# MPBoard_L4_Sens1_ext.net
KiCad netlist of a schematic drawn in Altium Designer
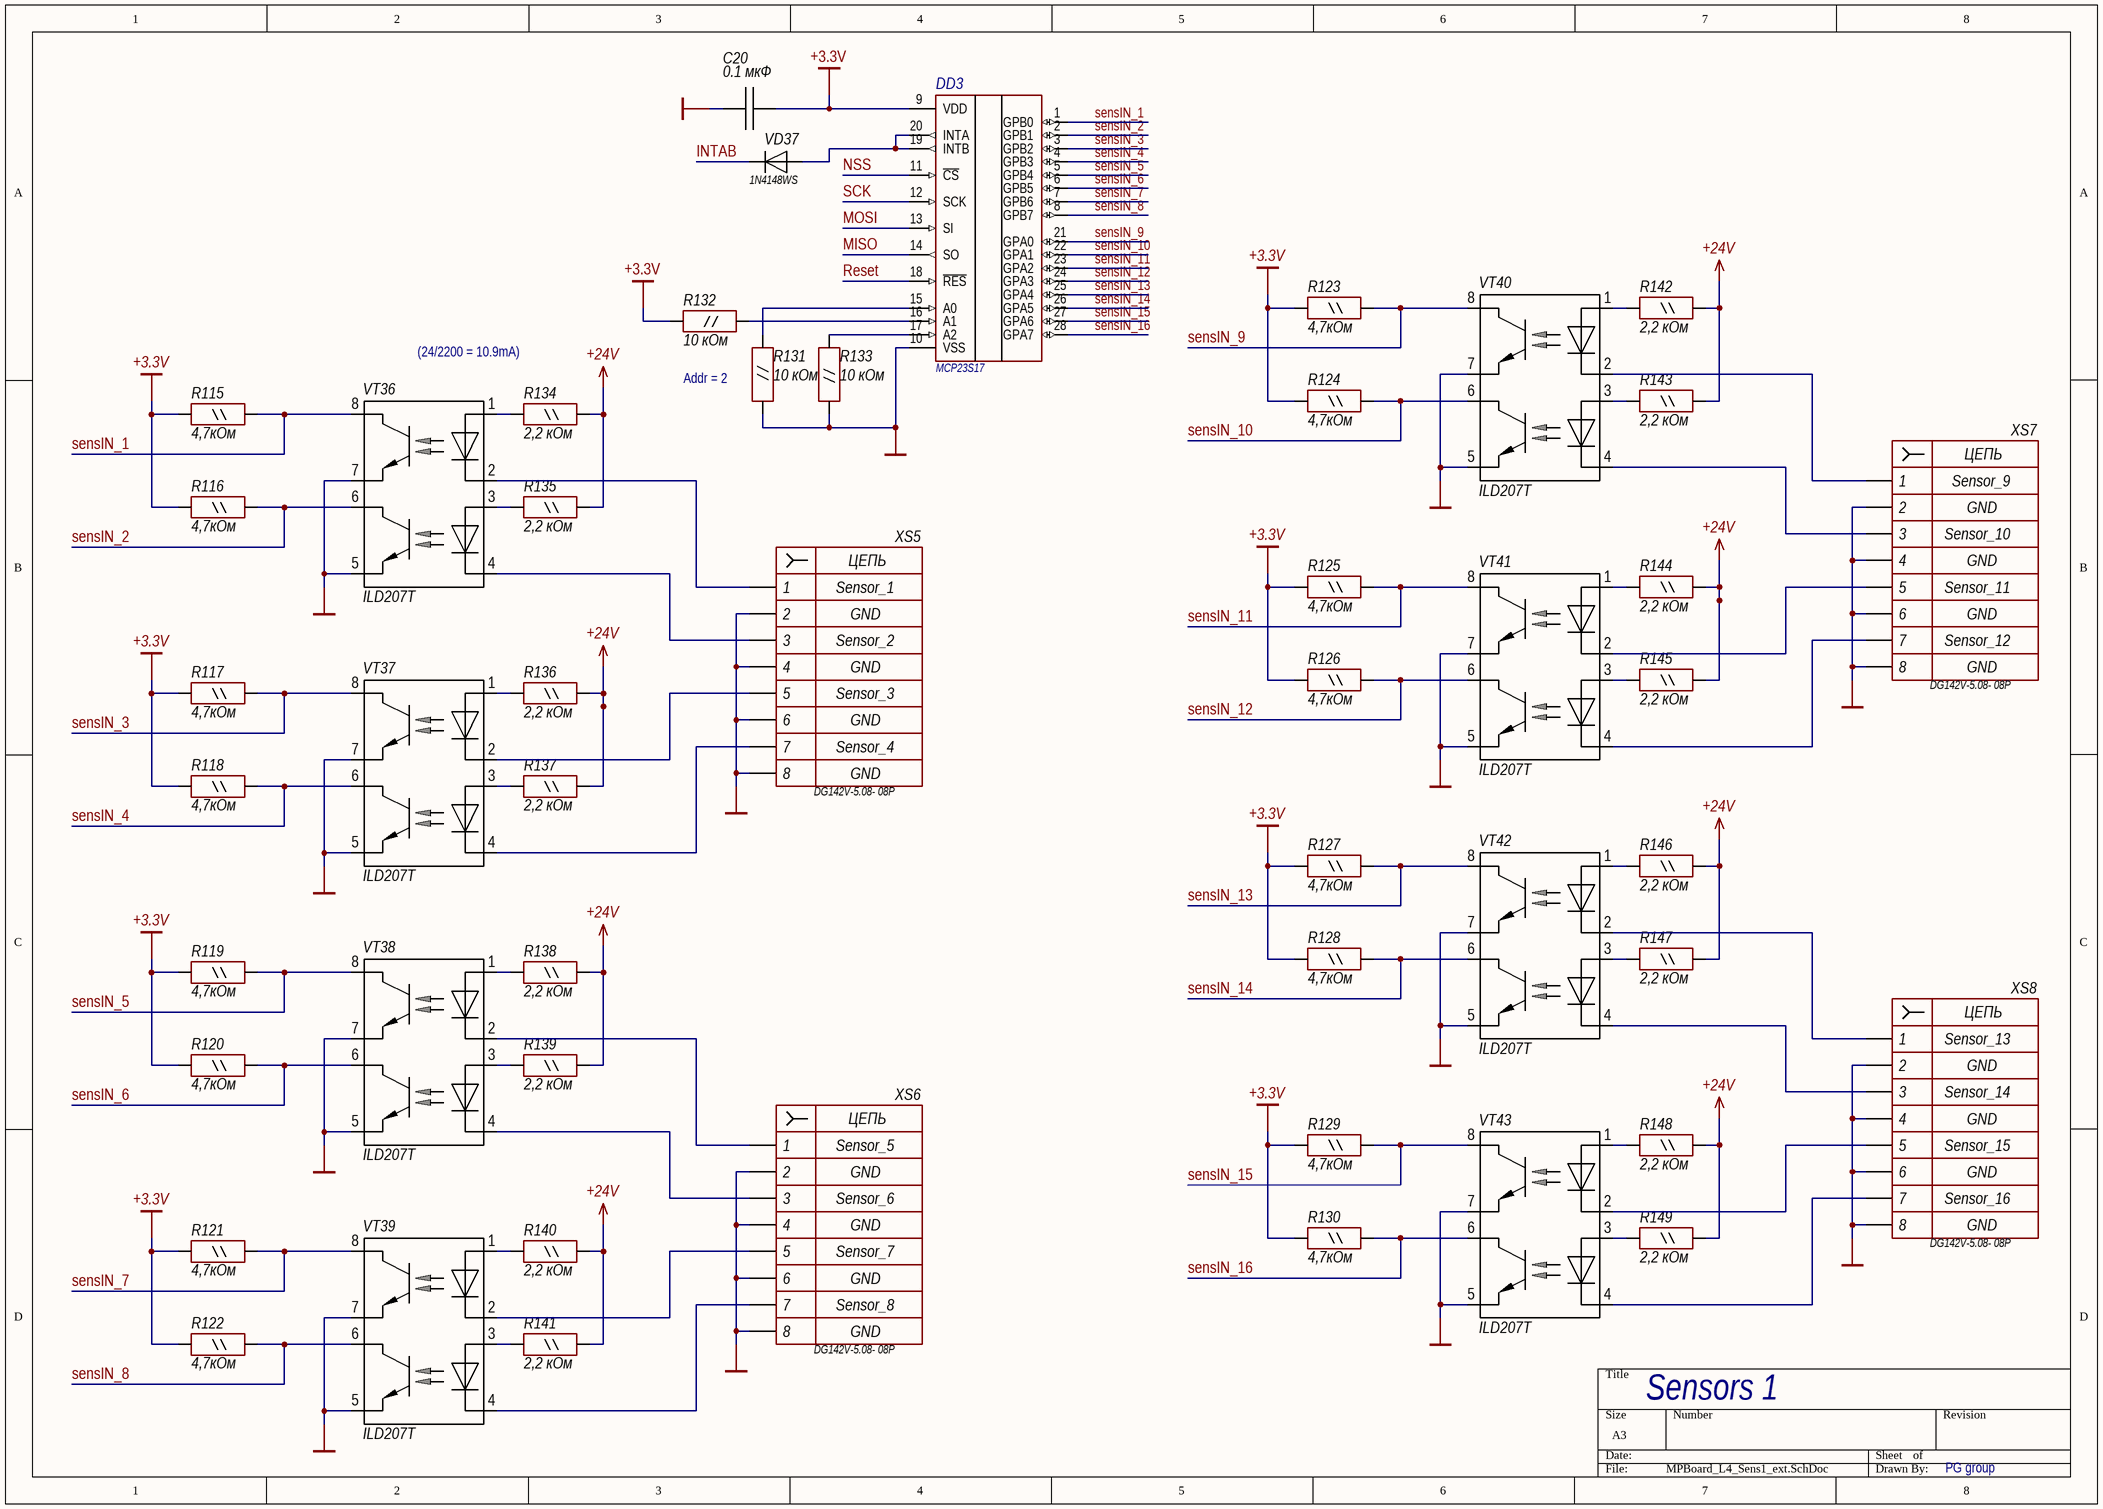
[diagram p0: MPBoard_L4_Sens1_ext.SchDoc]

(export (version "E")
  (design (tool "Eeschema 10.0.6"))
  (components
    (comp (ref "C20")
      (value "0.1 мкФ")
      (footprint "CAP-0603")
      (description "Конденсатор")
      (fields (field (name "MF") "KEMET") (field (name "TOLERANCE") "± 10 %"))
      (libsource (lib "MainBoard") (part "C"))
    )
    (comp (ref "DD3")
      (value "MCP23S17")
      (footprint "SOIC-28")
      (description "I/O Expander 16 SPI")
      (fields (field (name "MF") "Microchip"))
      (libsource (lib "MPBoard") (part "DD_MCP23S17"))
    )
    (comp (ref "R115")
      (value "4,7кОм")
      (footprint "RES-0603")
      (description "Резистор 0.1 W")
      (fields (field (name "MF") "Vishay") (field (name "TOLERANCE") "± 1 %"))
      (libsource (lib "") (part "R_0.125W_1"))
    )
    (comp (ref "R116")
      (value "4,7кОм")
      (footprint "RES-0603")
      (description "Резистор 0.1 W")
      (fields (field (name "MF") "Vishay") (field (name "TOLERANCE") "± 1 %"))
      (libsource (lib "MainBoard") (part "R_0.125W"))
    )
    (comp (ref "R117")
      (value "4,7кОм")
      (footprint "RES-0603")
      (description "Резистор 0.1 W")
      (fields (field (name "MF") "Vishay") (field (name "TOLERANCE") "± 1 %"))
      (libsource (lib "MainBoard") (part "R_0.125W"))
    )
    (comp (ref "R118")
      (value "4,7кОм")
      (footprint "RES-0603")
      (description "Резистор 0.1 W")
      (fields (field (name "MF") "Vishay") (field (name "TOLERANCE") "± 1 %"))
      (libsource (lib "MainBoard") (part "R_0.125W"))
    )
    (comp (ref "R119")
      (value "4,7кОм")
      (footprint "RES-0603")
      (description "Резистор 0.1 W")
      (fields (field (name "MF") "Vishay") (field (name "TOLERANCE") "± 1 %"))
      (libsource (lib "") (part "R_0.125W_3"))
    )
    (comp (ref "R120")
      (value "4,7кОм")
      (footprint "RES-0603")
      (description "Резистор 0.1 W")
      (fields (field (name "MF") "Vishay") (field (name "TOLERANCE") "± 1 %"))
      (libsource (lib "") (part "R_0.125W_3"))
    )
    (comp (ref "R121")
      (value "4,7кОм")
      (footprint "RES-0603")
      (description "Резистор 0.1 W")
      (fields (field (name "MF") "Vishay") (field (name "TOLERANCE") "± 1 %"))
      (libsource (lib "") (part "R_0.125W_4"))
    )
    (comp (ref "R122")
      (value "4,7кОм")
      (footprint "RES-0603")
      (description "Резистор 0.1 W")
      (fields (field (name "MF") "Vishay") (field (name "TOLERANCE") "± 1 %"))
      (libsource (lib "") (part "R_0.125W_4"))
    )
    (comp (ref "R123")
      (value "4,7кОм")
      (footprint "RES-0603")
      (description "Резистор 0.1 W")
      (fields (field (name "MF") "Vishay") (field (name "TOLERANCE") "± 1 %"))
      (libsource (lib "") (part "R_0.125W_1"))
    )
    (comp (ref "R124")
      (value "4,7кОм")
      (footprint "RES-0603")
      (description "Резистор 0.1 W")
      (fields (field (name "MF") "Vishay") (field (name "TOLERANCE") "± 1 %"))
      (libsource (lib "") (part "R_0.125W_1"))
    )
    (comp (ref "R125")
      (value "4,7кОм")
      (footprint "RES-0603")
      (description "Резистор 0.1 W")
      (fields (field (name "MF") "Vishay") (field (name "TOLERANCE") "± 1 %"))
      (libsource (lib "MainBoard") (part "R_0.125W"))
    )
    (comp (ref "R126")
      (value "4,7кОм")
      (footprint "RES-0603")
      (description "Резистор 0.1 W")
      (fields (field (name "MF") "Vishay") (field (name "TOLERANCE") "± 1 %"))
      (libsource (lib "MainBoard") (part "R_0.125W"))
    )
    (comp (ref "R127")
      (value "4,7кОм")
      (footprint "RES-0603")
      (description "Резистор 0.1 W")
      (fields (field (name "MF") "Vishay") (field (name "TOLERANCE") "± 1 %"))
      (libsource (lib "") (part "R_0.125W_3"))
    )
    (comp (ref "R128")
      (value "4,7кОм")
      (footprint "RES-0603")
      (description "Резистор 0.1 W")
      (fields (field (name "MF") "Vishay") (field (name "TOLERANCE") "± 1 %"))
      (libsource (lib "") (part "R_0.125W_3"))
    )
    (comp (ref "R129")
      (value "4,7кОм")
      (footprint "RES-0603")
      (description "Резистор 0.1 W")
      (fields (field (name "MF") "Vishay") (field (name "TOLERANCE") "± 1 %"))
      (libsource (lib "") (part "R_0.125W_3"))
    )
    (comp (ref "R130")
      (value "4,7кОм")
      (footprint "RES-0603")
      (description "Резистор 0.1 W")
      (fields (field (name "MF") "Vishay") (field (name "TOLERANCE") "± 1 %"))
      (libsource (lib "") (part "R_0.125W_4"))
    )
    (comp (ref "R131")
      (value "10 кОм")
      (footprint "RES-0603")
      (description "Резистор 0.1 W")
      (fields (field (name "MF") "Vishay") (field (name "TOLERANCE") "± 1 %"))
      (libsource (lib "") (part "R_0.125W_6"))
    )
    (comp (ref "R132")
      (value "10 кОм")
      (footprint "RES-0603")
      (description "Резистор 0.1 W")
      (fields (field (name "MF") "Vishay") (field (name "TOLERANCE") "± 1 %"))
      (libsource (lib "") (part "R_0.125W_2"))
    )
    (comp (ref "R133")
      (value "10 кОм")
      (footprint "RES-0603")
      (description "Резистор 0.1 W")
      (fields (field (name "MF") "Vishay") (field (name "TOLERANCE") "± 1 %"))
      (libsource (lib "") (part "R_0.125W_5"))
    )
    (comp (ref "R134")
      (value "2,2 кОм")
      (footprint "RES-0805")
      (description "Резистор 0.125 W")
      (fields (field (name "MF") "Vishay") (field (name "TOLERANCE") "± 1 %"))
      (libsource (lib "") (part "R_0.125W_1"))
    )
    (comp (ref "R135")
      (value "2,2 кОм")
      (footprint "RES-0805")
      (description "Резистор 0.125 W")
      (fields (field (name "MF") "Vishay") (field (name "TOLERANCE") "± 1 %"))
      (libsource (lib "MainBoard") (part "R_0.125W"))
    )
    (comp (ref "R136")
      (value "2,2 кОм")
      (footprint "RES-0805")
      (description "Резистор 0.125 W")
      (fields (field (name "MF") "Vishay") (field (name "TOLERANCE") "± 1 %"))
      (libsource (lib "MainBoard") (part "R_0.125W"))
    )
    (comp (ref "R137")
      (value "2,2 кОм")
      (footprint "RES-0805")
      (description "Резистор 0.125 W")
      (fields (field (name "MF") "Vishay") (field (name "TOLERANCE") "± 1 %"))
      (libsource (lib "MainBoard") (part "R_0.125W"))
    )
    (comp (ref "R138")
      (value "2,2 кОм")
      (footprint "RES-0805")
      (description "Резистор 0.125 W")
      (fields (field (name "MF") "Vishay") (field (name "TOLERANCE") "± 1 %"))
      (libsource (lib "") (part "R_0.125W_3"))
    )
    (comp (ref "R139")
      (value "2,2 кОм")
      (footprint "RES-0805")
      (description "Резистор 0.125 W")
      (fields (field (name "MF") "Vishay") (field (name "TOLERANCE") "± 1 %"))
      (libsource (lib "") (part "R_0.125W_3"))
    )
    (comp (ref "R140")
      (value "2,2 кОм")
      (footprint "RES-0805")
      (description "Резистор 0.125 W")
      (fields (field (name "MF") "Vishay") (field (name "TOLERANCE") "± 1 %"))
      (libsource (lib "") (part "R_0.125W_4"))
    )
    (comp (ref "R141")
      (value "2,2 кОм")
      (footprint "RES-0805")
      (description "Резистор 0.125 W")
      (fields (field (name "MF") "Vishay") (field (name "TOLERANCE") "± 1 %"))
      (libsource (lib "") (part "R_0.125W_4"))
    )
    (comp (ref "R142")
      (value "2,2 кОм")
      (footprint "RES-0805")
      (description "Резистор 0.125 W")
      (fields (field (name "MF") "Vishay") (field (name "TOLERANCE") "± 1 %"))
      (libsource (lib "") (part "R_0.125W_1"))
    )
    (comp (ref "R143")
      (value "2,2 кОм")
      (footprint "RES-0805")
      (description "Резистор 0.125 W")
      (fields (field (name "MF") "Vishay") (field (name "TOLERANCE") "± 1 %"))
      (libsource (lib "") (part "R_0.125W_1"))
    )
    (comp (ref "R144")
      (value "2,2 кОм")
      (footprint "RES-0805")
      (description "Резистор 0.125 W")
      (fields (field (name "MF") "Vishay") (field (name "TOLERANCE") "± 1 %"))
      (libsource (lib "MainBoard") (part "R_0.125W"))
    )
    (comp (ref "R145")
      (value "2,2 кОм")
      (footprint "RES-0805")
      (description "Резистор 0.125 W")
      (fields (field (name "MF") "Vishay") (field (name "TOLERANCE") "± 1 %"))
      (libsource (lib "MainBoard") (part "R_0.125W"))
    )
    (comp (ref "R146")
      (value "2,2 кОм")
      (footprint "RES-0805")
      (description "Резистор 0.125 W")
      (fields (field (name "MF") "Vishay") (field (name "TOLERANCE") "± 1 %"))
      (libsource (lib "") (part "R_0.125W_3"))
    )
    (comp (ref "R147")
      (value "2,2 кОм")
      (footprint "RES-0805")
      (description "Резистор 0.125 W")
      (fields (field (name "MF") "Vishay") (field (name "TOLERANCE") "± 1 %"))
      (libsource (lib "") (part "R_0.125W_3"))
    )
    (comp (ref "R148")
      (value "2,2 кОм")
      (footprint "RES-0805")
      (description "Резистор 0.125 W")
      (fields (field (name "MF") "Vishay") (field (name "TOLERANCE") "± 1 %"))
      (libsource (lib "") (part "R_0.125W_3"))
    )
    (comp (ref "R149")
      (value "2,2 кОм")
      (footprint "RES-0805")
      (description "Резистор 0.125 W")
      (fields (field (name "MF") "Vishay") (field (name "TOLERANCE") "± 1 %"))
      (libsource (lib "") (part "R_0.125W_4"))
    )
    (comp (ref "VD37")
      (value "1N4148WS")
      (footprint "SOD-323")
      (description "Диод Выпрямительный")
      (fields (field (name "MF") "Diotec Semiconductor"))
      (libsource (lib "MPBoard") (part "VD"))
    )
    (comp (ref "VT36")
      (value "ILD207T")
      (footprint "SOIC-8")
      (description "Оптопара")
      (fields (field (name "MF") "Vishay"))
      (libsource (lib "MPBoard") (part "VT_2xOPTOCOUPLER"))
    )
    (comp (ref "VT37")
      (value "ILD207T")
      (footprint "SOIC-8")
      (description "Оптопара")
      (fields (field (name "MF") "Vishay"))
      (libsource (lib "MPBoard") (part "VT_2xOPTOCOUPLER"))
    )
    (comp (ref "VT38")
      (value "ILD207T")
      (footprint "SOIC-8")
      (description "Оптопара")
      (fields (field (name "MF") "Vishay"))
      (libsource (lib "MPBoard") (part "VT_2xOPTOCOUPLER"))
    )
    (comp (ref "VT39")
      (value "ILD207T")
      (footprint "SOIC-8")
      (description "Оптопара")
      (fields (field (name "MF") "Vishay"))
      (libsource (lib "MPBoard") (part "VT_2xOPTOCOUPLER"))
    )
    (comp (ref "VT40")
      (value "ILD207T")
      (footprint "SOIC-8")
      (description "Оптопара")
      (fields (field (name "MF") "Vishay"))
      (libsource (lib "MPBoard") (part "VT_2xOPTOCOUPLER"))
    )
    (comp (ref "VT41")
      (value "ILD207T")
      (footprint "SOIC-8")
      (description "Оптопара")
      (fields (field (name "MF") "Vishay"))
      (libsource (lib "MPBoard") (part "VT_2xOPTOCOUPLER"))
    )
    (comp (ref "VT42")
      (value "ILD207T")
      (footprint "SOIC-8")
      (description "Оптопара")
      (fields (field (name "MF") "Vishay"))
      (libsource (lib "MPBoard") (part "VT_2xOPTOCOUPLER"))
    )
    (comp (ref "VT43")
      (value "ILD207T")
      (footprint "SOIC-8")
      (description "Оптопара")
      (fields (field (name "MF") "Vishay"))
      (libsource (lib "MPBoard") (part "VT_2xOPTOCOUPLER"))
    )
    (comp (ref "XS5")
      (value "DG142V-5.08- 08P")
      (footprint "DG142V-5.08-08")
      (description "розетка 8 контактов")
      (fields
        (field (name "MF") "Degson Electronics")
        (field (name "MFPARTNUM") "DG142V-5.08- 08P-14-00A(H)")
        (field (name "NET6") "GND")
        (field (name "NET5") "Sensor_3")
        (field (name "NET1") "Sensor_1")
        (field (name "NET2") "GND")
        (field (name "NET3") "Sensor_2")
        (field (name "NET4") "GND")
        (field (name "NET7") "Sensor_4")
        (field (name "NET8") "GND")
      )
      (libsource (lib "MPBoard") (part "XS8"))
    )
    (comp (ref "XS6")
      (value "DG142V-5.08- 08P")
      (footprint "DG142V-5.08-08")
      (description "розетка 8 контактов")
      (fields
        (field (name "MF") "Degson Electronics")
        (field (name "MFPARTNUM") "DG142V-5.08- 08P-14-00A(H)")
        (field (name "NET6") "GND")
        (field (name "NET5") "Sensor_7")
        (field (name "NET1") "Sensor_5")
        (field (name "NET2") "GND")
        (field (name "NET3") "Sensor_6")
        (field (name "NET4") "GND")
        (field (name "NET7") "Sensor_8")
        (field (name "NET8") "GND")
      )
      (libsource (lib "MPBoard") (part "XS8"))
    )
    (comp (ref "XS7")
      (value "DG142V-5.08- 08P")
      (footprint "DG142V-5.08-08")
      (description "розетка 8 контактов")
      (fields
        (field (name "MF") "Degson Electronics")
        (field (name "MFPARTNUM") "DG142V-5.08- 08P-14-00A(H)")
        (field (name "NET6") "GND")
        (field (name "NET5") "Sensor_11")
        (field (name "NET1") "Sensor_9")
        (field (name "NET2") "GND")
        (field (name "NET3") "Sensor_10")
        (field (name "NET4") "GND")
        (field (name "NET7") "Sensor_12")
        (field (name "NET8") "GND")
      )
      (libsource (lib "MPBoard") (part "XS8"))
    )
    (comp (ref "XS8")
      (value "DG142V-5.08- 08P")
      (footprint "DG142V-5.08-08")
      (description "розетка 8 контактов")
      (fields
        (field (name "MF") "Degson Electronics")
        (field (name "MFPARTNUM") "DG142V-5.08- 08P-14-00A(H)")
        (field (name "NET6") "GND")
        (field (name "NET5") "Sensor_15")
        (field (name "NET1") "Sensor_13")
        (field (name "NET2") "GND")
        (field (name "NET3") "Sensor_14")
        (field (name "NET4") "GND")
        (field (name "NET7") "Sensor_16")
        (field (name "NET8") "GND")
      )
      (libsource (lib "MPBoard") (part "XS8"))
    )
  )
  (nets
    (net (code "1") (name "+3.3V") (class "Default")
      (node (ref "C20") (pin "2") (pinfunction "2_2") (pintype "passive"))
      (node (ref "DD3") (pin "9") (pinfunction "VDD_9") (pintype "power_in"))
      (node (ref "R115") (pin "2") (pinfunction "2_2") (pintype "passive"))
      (node (ref "R116") (pin "2") (pinfunction "2_2") (pintype "passive"))
      (node (ref "R117") (pin "2") (pinfunction "2_2") (pintype "passive"))
      (node (ref "R118") (pin "2") (pinfunction "2_2") (pintype "passive"))
      (node (ref "R119") (pin "2") (pinfunction "2_2") (pintype "passive"))
      (node (ref "R120") (pin "2") (pinfunction "2_2") (pintype "passive"))
      (node (ref "R121") (pin "2") (pinfunction "2_2") (pintype "passive"))
      (node (ref "R122") (pin "2") (pinfunction "2_2") (pintype "passive"))
      (node (ref "R123") (pin "2") (pinfunction "2_2") (pintype "passive"))
      (node (ref "R124") (pin "2") (pinfunction "2_2") (pintype "passive"))
      (node (ref "R125") (pin "2") (pinfunction "2_2") (pintype "passive"))
      (node (ref "R126") (pin "2") (pinfunction "2_2") (pintype "passive"))
      (node (ref "R127") (pin "2") (pinfunction "2_2") (pintype "passive"))
      (node (ref "R128") (pin "2") (pinfunction "2_2") (pintype "passive"))
      (node (ref "R129") (pin "2") (pinfunction "2_2") (pintype "passive"))
      (node (ref "R130") (pin "2") (pinfunction "2_2") (pintype "passive"))
      (node (ref "R132") (pin "2") (pinfunction "2_2") (pintype "passive"))
    )
    (net (code "2") (name "+24V") (class "Default")
      (node (ref "R134") (pin "1") (pinfunction "1_1") (pintype "passive"))
      (node (ref "R135") (pin "1") (pinfunction "1_1") (pintype "passive"))
      (node (ref "R136") (pin "1") (pinfunction "1_1") (pintype "passive"))
      (node (ref "R137") (pin "1") (pinfunction "1_1") (pintype "passive"))
      (node (ref "R138") (pin "1") (pinfunction "1_1") (pintype "passive"))
      (node (ref "R139") (pin "1") (pinfunction "1_1") (pintype "passive"))
      (node (ref "R140") (pin "1") (pinfunction "1_1") (pintype "passive"))
      (node (ref "R141") (pin "1") (pinfunction "1_1") (pintype "passive"))
      (node (ref "R142") (pin "1") (pinfunction "1_1") (pintype "passive"))
      (node (ref "R143") (pin "1") (pinfunction "1_1") (pintype "passive"))
      (node (ref "R144") (pin "1") (pinfunction "1_1") (pintype "passive"))
      (node (ref "R145") (pin "1") (pinfunction "1_1") (pintype "passive"))
      (node (ref "R146") (pin "1") (pinfunction "1_1") (pintype "passive"))
      (node (ref "R147") (pin "1") (pinfunction "1_1") (pintype "passive"))
      (node (ref "R148") (pin "1") (pinfunction "1_1") (pintype "passive"))
      (node (ref "R149") (pin "1") (pinfunction "1_1") (pintype "passive"))
    )
    (net (code "3") (name "/INTAB") (class "Default")
      (node (ref "VD37") (pin "2") (pinfunction "2_2") (pintype "passive"))
    )
    (net (code "4") (name "/MISO") (class "Default")
      (node (ref "DD3") (pin "14") (pinfunction "SO_14") (pintype "output"))
    )
    (net (code "5") (name "/MOSI") (class "Default")
      (node (ref "DD3") (pin "13") (pinfunction "SI_13") (pintype "input"))
    )
    (net (code "6") (name "/NSS") (class "Default")
      (node (ref "DD3") (pin "11") (pinfunction "~{CS}_11") (pintype "input"))
    )
    (net (code "7") (name "/Reset") (class "Default")
      (node (ref "DD3") (pin "18") (pinfunction "~{RES}_18") (pintype "input"))
    )
    (net (code "8") (name "/SCK") (class "Default")
      (node (ref "DD3") (pin "12") (pinfunction "SCK_12") (pintype "input"))
    )
    (net (code "9") (name "/sensIN_1") (class "Default")
      (node (ref "DD3") (pin "1") (pinfunction "GPB0_1") (pintype "bidirectional"))
      (node (ref "R115") (pin "1") (pinfunction "1_1") (pintype "passive"))
      (node (ref "VT36") (pin "8") (pintype "passive"))
    )
    (net (code "10") (name "/sensIN_2") (class "Default")
      (node (ref "DD3") (pin "2") (pinfunction "GPB1_2") (pintype "bidirectional"))
      (node (ref "R116") (pin "1") (pinfunction "1_1") (pintype "passive"))
      (node (ref "VT36") (pin "6") (pintype "passive"))
    )
    (net (code "11") (name "/sensIN_3") (class "Default")
      (node (ref "DD3") (pin "3") (pinfunction "GPB2_3") (pintype "bidirectional"))
      (node (ref "R117") (pin "1") (pinfunction "1_1") (pintype "passive"))
      (node (ref "VT37") (pin "8") (pintype "passive"))
    )
    (net (code "12") (name "/sensIN_4") (class "Default")
      (node (ref "DD3") (pin "4") (pinfunction "GPB3_4") (pintype "bidirectional"))
      (node (ref "R118") (pin "1") (pinfunction "1_1") (pintype "passive"))
      (node (ref "VT37") (pin "6") (pintype "passive"))
    )
    (net (code "13") (name "/sensIN_5") (class "Default")
      (node (ref "DD3") (pin "5") (pinfunction "GPB4_5") (pintype "bidirectional"))
      (node (ref "R119") (pin "1") (pinfunction "1_1") (pintype "passive"))
      (node (ref "VT38") (pin "8") (pintype "passive"))
    )
    (net (code "14") (name "/sensIN_6") (class "Default")
      (node (ref "DD3") (pin "6") (pinfunction "GPB5_6") (pintype "bidirectional"))
      (node (ref "R120") (pin "1") (pinfunction "1_1") (pintype "passive"))
      (node (ref "VT38") (pin "6") (pintype "passive"))
    )
    (net (code "15") (name "/sensIN_7") (class "Default")
      (node (ref "DD3") (pin "7") (pinfunction "GPB6_7") (pintype "bidirectional"))
      (node (ref "R121") (pin "1") (pinfunction "1_1") (pintype "passive"))
      (node (ref "VT39") (pin "8") (pintype "passive"))
    )
    (net (code "16") (name "/sensIN_8") (class "Default")
      (node (ref "DD3") (pin "8") (pinfunction "GPB7_8") (pintype "bidirectional"))
      (node (ref "R122") (pin "1") (pinfunction "1_1") (pintype "passive"))
      (node (ref "VT39") (pin "6") (pintype "passive"))
    )
    (net (code "17") (name "/sensIN_9") (class "Default")
      (node (ref "DD3") (pin "21") (pinfunction "GPA0_21") (pintype "bidirectional"))
      (node (ref "R123") (pin "1") (pinfunction "1_1") (pintype "passive"))
      (node (ref "VT40") (pin "8") (pintype "passive"))
    )
    (net (code "18") (name "/sensIN_10") (class "Default")
      (node (ref "DD3") (pin "22") (pinfunction "GPA1_22") (pintype "bidirectional"))
      (node (ref "R124") (pin "1") (pinfunction "1_1") (pintype "passive"))
      (node (ref "VT40") (pin "6") (pintype "passive"))
    )
    (net (code "19") (name "/sensIN_11") (class "Default")
      (node (ref "DD3") (pin "23") (pinfunction "GPA2_23") (pintype "bidirectional"))
      (node (ref "R125") (pin "1") (pinfunction "1_1") (pintype "passive"))
      (node (ref "VT41") (pin "8") (pintype "passive"))
    )
    (net (code "20") (name "/sensIN_12") (class "Default")
      (node (ref "DD3") (pin "24") (pinfunction "GPA3_24") (pintype "bidirectional"))
      (node (ref "R126") (pin "1") (pinfunction "1_1") (pintype "passive"))
      (node (ref "VT41") (pin "6") (pintype "passive"))
    )
    (net (code "21") (name "/sensIN_13") (class "Default")
      (node (ref "DD3") (pin "25") (pinfunction "GPA4_25") (pintype "bidirectional"))
      (node (ref "R127") (pin "1") (pinfunction "1_1") (pintype "passive"))
      (node (ref "VT42") (pin "8") (pintype "passive"))
    )
    (net (code "22") (name "/sensIN_14") (class "Default")
      (node (ref "DD3") (pin "26") (pinfunction "GPA5_26") (pintype "bidirectional"))
      (node (ref "R128") (pin "1") (pinfunction "1_1") (pintype "passive"))
      (node (ref "VT42") (pin "6") (pintype "passive"))
    )
    (net (code "23") (name "/sensIN_15") (class "Default")
      (node (ref "DD3") (pin "27") (pinfunction "GPA6_27") (pintype "bidirectional"))
      (node (ref "R129") (pin "1") (pinfunction "1_1") (pintype "passive"))
      (node (ref "VT43") (pin "8") (pintype "passive"))
    )
    (net (code "24") (name "/sensIN_16") (class "Default")
      (node (ref "DD3") (pin "28") (pinfunction "GPA7_28") (pintype "bidirectional"))
      (node (ref "R130") (pin "1") (pinfunction "1_1") (pintype "passive"))
      (node (ref "VT43") (pin "6") (pintype "passive"))
    )
    (net (code "25") (name "GND") (class "Default")
      (node (ref "C20") (pin "1") (pinfunction "1_1") (pintype "passive"))
      (node (ref "DD3") (pin "10") (pinfunction "VSS_10") (pintype "power_in"))
      (node (ref "R131") (pin "2") (pinfunction "2_2") (pintype "passive"))
      (node (ref "R133") (pin "1") (pinfunction "1_1") (pintype "passive"))
      (node (ref "VT36") (pin "5") (pintype "passive"))
      (node (ref "VT36") (pin "7") (pintype "passive"))
      (node (ref "VT37") (pin "5") (pintype "passive"))
      (node (ref "VT37") (pin "7") (pintype "passive"))
      (node (ref "VT38") (pin "5") (pintype "passive"))
      (node (ref "VT38") (pin "7") (pintype "passive"))
      (node (ref "VT39") (pin "5") (pintype "passive"))
      (node (ref "VT39") (pin "7") (pintype "passive"))
      (node (ref "VT40") (pin "5") (pintype "passive"))
      (node (ref "VT40") (pin "7") (pintype "passive"))
      (node (ref "VT41") (pin "5") (pintype "passive"))
      (node (ref "VT41") (pin "7") (pintype "passive"))
      (node (ref "VT42") (pin "5") (pintype "passive"))
      (node (ref "VT42") (pin "7") (pintype "passive"))
      (node (ref "VT43") (pin "5") (pintype "passive"))
      (node (ref "VT43") (pin "7") (pintype "passive"))
      (node (ref "XS5") (pin "2") (pinfunction "2_2") (pintype "passive"))
      (node (ref "XS5") (pin "4") (pinfunction "4_4") (pintype "passive"))
      (node (ref "XS5") (pin "6") (pinfunction "6_6") (pintype "passive"))
      (node (ref "XS5") (pin "8") (pinfunction "8_8") (pintype "passive"))
      (node (ref "XS6") (pin "2") (pinfunction "2_2") (pintype "passive"))
      (node (ref "XS6") (pin "4") (pinfunction "4_4") (pintype "passive"))
      (node (ref "XS6") (pin "6") (pinfunction "6_6") (pintype "passive"))
      (node (ref "XS6") (pin "8") (pinfunction "8_8") (pintype "passive"))
      (node (ref "XS7") (pin "2") (pinfunction "2_2") (pintype "passive"))
      (node (ref "XS7") (pin "4") (pinfunction "4_4") (pintype "passive"))
      (node (ref "XS7") (pin "6") (pinfunction "6_6") (pintype "passive"))
      (node (ref "XS7") (pin "8") (pinfunction "8_8") (pintype "passive"))
      (node (ref "XS8") (pin "2") (pinfunction "2_2") (pintype "passive"))
      (node (ref "XS8") (pin "4") (pinfunction "4_4") (pintype "passive"))
      (node (ref "XS8") (pin "6") (pinfunction "6_6") (pintype "passive"))
      (node (ref "XS8") (pin "8") (pinfunction "8_8") (pintype "passive"))
    )
    (net (code "26") (name "Net-(DD3-A0)") (class "Default")
      (node (ref "DD3") (pin "15") (pinfunction "A0_15") (pintype "input"))
      (node (ref "R131") (pin "1") (pinfunction "1_1") (pintype "passive"))
    )
    (net (code "27") (name "Net-(DD3-A1)") (class "Default")
      (node (ref "DD3") (pin "16") (pinfunction "A1_16") (pintype "input"))
      (node (ref "R132") (pin "1") (pinfunction "1_1") (pintype "passive"))
    )
    (net (code "28") (name "Net-(DD3-A2)") (class "Default")
      (node (ref "DD3") (pin "17") (pinfunction "A2_17") (pintype "input"))
      (node (ref "R133") (pin "2") (pinfunction "2_2") (pintype "passive"))
    )
    (net (code "29") (name "Net-(DD3-INTA)") (class "Default")
      (node (ref "DD3") (pin "19") (pinfunction "INTB_19") (pintype "output"))
      (node (ref "DD3") (pin "20") (pinfunction "INTA_20") (pintype "output"))
      (node (ref "VD37") (pin "1") (pinfunction "1_1") (pintype "passive"))
    )
    (net (code "30") (name "Net-(R134-Pad2)") (class "Default")
      (node (ref "R134") (pin "2") (pinfunction "2_2") (pintype "passive"))
      (node (ref "VT36") (pin "1") (pintype "passive"))
    )
    (net (code "31") (name "Net-(R135-Pad2)") (class "Default")
      (node (ref "R135") (pin "2") (pinfunction "2_2") (pintype "passive"))
      (node (ref "VT36") (pin "3") (pintype "passive"))
    )
    (net (code "32") (name "Net-(R136-Pad2)") (class "Default")
      (node (ref "R136") (pin "2") (pinfunction "2_2") (pintype "passive"))
      (node (ref "VT37") (pin "1") (pintype "passive"))
    )
    (net (code "33") (name "Net-(R137-Pad2)") (class "Default")
      (node (ref "R137") (pin "2") (pinfunction "2_2") (pintype "passive"))
      (node (ref "VT37") (pin "3") (pintype "passive"))
    )
    (net (code "34") (name "Net-(R138-Pad2)") (class "Default")
      (node (ref "R138") (pin "2") (pinfunction "2_2") (pintype "passive"))
      (node (ref "VT38") (pin "1") (pintype "passive"))
    )
    (net (code "35") (name "Net-(R139-Pad2)") (class "Default")
      (node (ref "R139") (pin "2") (pinfunction "2_2") (pintype "passive"))
      (node (ref "VT38") (pin "3") (pintype "passive"))
    )
    (net (code "36") (name "Net-(R140-Pad2)") (class "Default")
      (node (ref "R140") (pin "2") (pinfunction "2_2") (pintype "passive"))
      (node (ref "VT39") (pin "1") (pintype "passive"))
    )
    (net (code "37") (name "Net-(R141-Pad2)") (class "Default")
      (node (ref "R141") (pin "2") (pinfunction "2_2") (pintype "passive"))
      (node (ref "VT39") (pin "3") (pintype "passive"))
    )
    (net (code "38") (name "Net-(R142-Pad2)") (class "Default")
      (node (ref "R142") (pin "2") (pinfunction "2_2") (pintype "passive"))
      (node (ref "VT40") (pin "1") (pintype "passive"))
    )
    (net (code "39") (name "Net-(R143-Pad2)") (class "Default")
      (node (ref "R143") (pin "2") (pinfunction "2_2") (pintype "passive"))
      (node (ref "VT40") (pin "3") (pintype "passive"))
    )
    (net (code "40") (name "Net-(R144-Pad2)") (class "Default")
      (node (ref "R144") (pin "2") (pinfunction "2_2") (pintype "passive"))
      (node (ref "VT41") (pin "1") (pintype "passive"))
    )
    (net (code "41") (name "Net-(R145-Pad2)") (class "Default")
      (node (ref "R145") (pin "2") (pinfunction "2_2") (pintype "passive"))
      (node (ref "VT41") (pin "3") (pintype "passive"))
    )
    (net (code "42") (name "Net-(R146-Pad2)") (class "Default")
      (node (ref "R146") (pin "2") (pinfunction "2_2") (pintype "passive"))
      (node (ref "VT42") (pin "1") (pintype "passive"))
    )
    (net (code "43") (name "Net-(R147-Pad2)") (class "Default")
      (node (ref "R147") (pin "2") (pinfunction "2_2") (pintype "passive"))
      (node (ref "VT42") (pin "3") (pintype "passive"))
    )
    (net (code "44") (name "Net-(R148-Pad2)") (class "Default")
      (node (ref "R148") (pin "2") (pinfunction "2_2") (pintype "passive"))
      (node (ref "VT43") (pin "1") (pintype "passive"))
    )
    (net (code "45") (name "Net-(R149-Pad2)") (class "Default")
      (node (ref "R149") (pin "2") (pinfunction "2_2") (pintype "passive"))
      (node (ref "VT43") (pin "3") (pintype "passive"))
    )
    (net (code "46") (name "Net-(VT36-Pad2)") (class "Default")
      (node (ref "VT36") (pin "2") (pintype "passive"))
      (node (ref "XS5") (pin "1") (pinfunction "1_1") (pintype "passive"))
    )
    (net (code "47") (name "Net-(VT36-Pad4)") (class "Default")
      (node (ref "VT36") (pin "4") (pintype "passive"))
      (node (ref "XS5") (pin "3") (pinfunction "3_3") (pintype "passive"))
    )
    (net (code "48") (name "Net-(VT37-Pad2)") (class "Default")
      (node (ref "VT37") (pin "2") (pintype "passive"))
      (node (ref "XS5") (pin "5") (pinfunction "5_5") (pintype "passive"))
    )
    (net (code "49") (name "Net-(VT37-Pad4)") (class "Default")
      (node (ref "VT37") (pin "4") (pintype "passive"))
      (node (ref "XS5") (pin "7") (pinfunction "7_7") (pintype "passive"))
    )
    (net (code "50") (name "Net-(VT38-Pad2)") (class "Default")
      (node (ref "VT38") (pin "2") (pintype "passive"))
      (node (ref "XS6") (pin "1") (pinfunction "1_1") (pintype "passive"))
    )
    (net (code "51") (name "Net-(VT38-Pad4)") (class "Default")
      (node (ref "VT38") (pin "4") (pintype "passive"))
      (node (ref "XS6") (pin "3") (pinfunction "3_3") (pintype "passive"))
    )
    (net (code "52") (name "Net-(VT39-Pad2)") (class "Default")
      (node (ref "VT39") (pin "2") (pintype "passive"))
      (node (ref "XS6") (pin "5") (pinfunction "5_5") (pintype "passive"))
    )
    (net (code "53") (name "Net-(VT39-Pad4)") (class "Default")
      (node (ref "VT39") (pin "4") (pintype "passive"))
      (node (ref "XS6") (pin "7") (pinfunction "7_7") (pintype "passive"))
    )
    (net (code "54") (name "Net-(VT40-Pad2)") (class "Default")
      (node (ref "VT40") (pin "2") (pintype "passive"))
      (node (ref "XS7") (pin "1") (pinfunction "1_1") (pintype "passive"))
    )
    (net (code "55") (name "Net-(VT40-Pad4)") (class "Default")
      (node (ref "VT40") (pin "4") (pintype "passive"))
      (node (ref "XS7") (pin "3") (pinfunction "3_3") (pintype "passive"))
    )
    (net (code "56") (name "Net-(VT41-Pad2)") (class "Default")
      (node (ref "VT41") (pin "2") (pintype "passive"))
      (node (ref "XS7") (pin "5") (pinfunction "5_5") (pintype "passive"))
    )
    (net (code "57") (name "Net-(VT41-Pad4)") (class "Default")
      (node (ref "VT41") (pin "4") (pintype "passive"))
      (node (ref "XS7") (pin "7") (pinfunction "7_7") (pintype "passive"))
    )
    (net (code "58") (name "Net-(VT42-Pad2)") (class "Default")
      (node (ref "VT42") (pin "2") (pintype "passive"))
      (node (ref "XS8") (pin "1") (pinfunction "1_1") (pintype "passive"))
    )
    (net (code "59") (name "Net-(VT42-Pad4)") (class "Default")
      (node (ref "VT42") (pin "4") (pintype "passive"))
      (node (ref "XS8") (pin "3") (pinfunction "3_3") (pintype "passive"))
    )
    (net (code "60") (name "Net-(VT43-Pad2)") (class "Default")
      (node (ref "VT43") (pin "2") (pintype "passive"))
      (node (ref "XS8") (pin "5") (pinfunction "5_5") (pintype "passive"))
    )
    (net (code "61") (name "Net-(VT43-Pad4)") (class "Default")
      (node (ref "VT43") (pin "4") (pintype "passive"))
      (node (ref "XS8") (pin "7") (pinfunction "7_7") (pintype "passive"))
    )
  )
)
